# Radio_Controller.net
KiCad netlist of a schematic drawn in Altium Designer
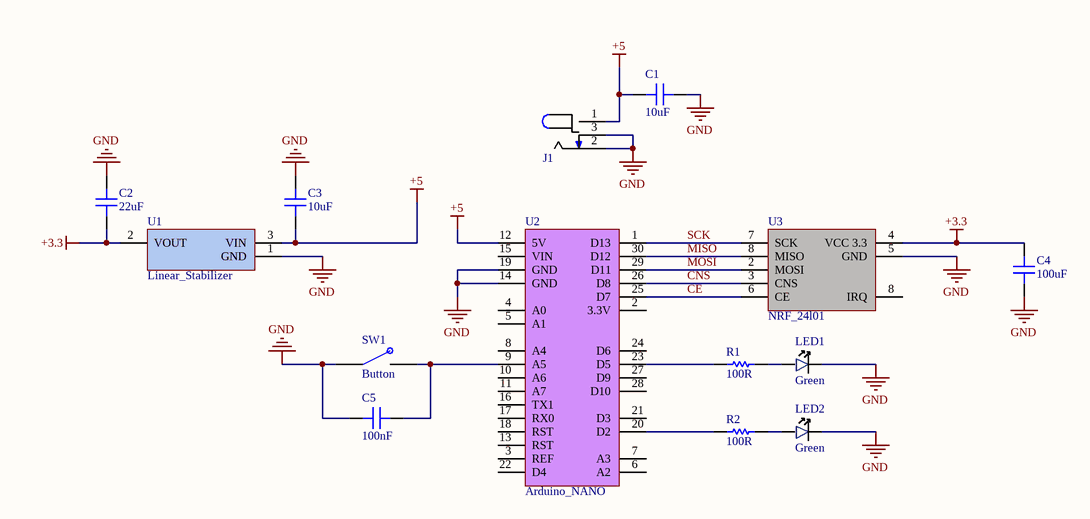
[diagram p0: Radio_Controller.SchDoc]

(export (version "E")
  (design (tool "Eeschema 10.0.6"))
  (components
    (comp (ref "C1")
      (value "10uF")
      (footprint "CAP 1206")
      (description "SMT Capacitor")
      (libsource (lib "Schlib1") (part "Capacitor"))
    )
    (comp (ref "C2")
      (value "22uF")
      (footprint "CAP 1206")
      (description "SMT Capacitor")
      (libsource (lib "Schlib1") (part "Capacitor"))
    )
    (comp (ref "C3")
      (value "10uF")
      (footprint "CAP 1206")
      (description "SMT Capacitor")
      (libsource (lib "Schlib1") (part "Capacitor"))
    )
    (comp (ref "C4")
      (value "100uF")
      (footprint "CAP 1206")
      (description "SMT Capacitor")
      (libsource (lib "Schlib1") (part "Capacitor"))
    )
    (comp (ref "C5")
      (value "100nF")
      (footprint "CAP 0603")
      (description "SMT Capacitor")
      (libsource (lib "Schlib1") (part "Capacitor"))
    )
    (comp (ref "J1")
      (value "Power Jack")
      (footprint "Power_Jack")
      (description "Power Barrel Connector Jack 2.10mm ID (0.083\"), 5.50mm OD (0.217\") Through Hole, Right Angle")
      (fields (field (name "MFR PART #") "PJ-102A") (field (name "LCSC PART#") "C136744"))
      (libsource (lib "Radio_Controller") (part "P_Power Jack"))
    )
    (comp (ref "LED1")
      (value "Green")
      (footprint "LED_0603")
      (description "LIGHT EMITTING DIODES (LED) GREEN 520~535NM 112~258MCD@20MA TOP VIEW 0603 ROHS")
      (fields (field (name "MFR PART #") "19-217/GHC-YR1S2/3T") (field (name "LCSC PART#") "C72043"))
      (libsource (lib "Radio_Controller") (part "LED_GREEN_0603"))
    )
    (comp (ref "LED2")
      (value "Green")
      (footprint "LED_0603")
      (description "LIGHT EMITTING DIODES (LED) GREEN 520~535NM 112~258MCD@20MA TOP VIEW 0603 ROHS")
      (fields (field (name "MFR PART #") "19-217/GHC-YR1S2/3T") (field (name "LCSC PART#") "C72043"))
      (libsource (lib "Radio_Controller") (part "LED_GREEN_0603"))
    )
    (comp (ref "R1")
      (value "100R")
      (footprint "RES 0603")
      (description "Resistor")
      (fields (field (name "PUBLISHER") "Altium Limited"))
      (libsource (lib "Radio_Controller") (part "Res"))
    )
    (comp (ref "R2")
      (value "100R")
      (footprint "RES 0603")
      (description "Resistor")
      (fields (field (name "PUBLISHER") "Altium Limited"))
      (libsource (lib "Radio_Controller") (part "Res"))
    )
    (comp (ref "SW1")
      (value "Button")
      (footprint "Button")
      (libsource (lib "Radio_Controller") (part "Button"))
    )
    (comp (ref "U1")
      (value "Linear_Stabilizer")
      (footprint "TO-220")
      (libsource (lib "Schlib1") (part "Linear_Stabilizer"))
    )
    (comp (ref "U2")
      (value "Arduino_NANO")
      (footprint "MODULE_ABX00028")
      (libsource (lib "Radio_Controller") (part "Arduino_NANO"))
    )
    (comp (ref "U3")
      (value "NRF_24l01")
      (footprint "NRF24L01")
      (libsource (lib "Schlib1") (part "NRF_24l01"))
    )
  )
  (nets
    (net (code "1") (name "+3.3") (class "Default")
      (node (ref "C2") (pin "2") (pinfunction "2_2") (pintype "passive"))
      (node (ref "C4") (pin "1") (pinfunction "1_1") (pintype "passive"))
      (node (ref "U1") (pin "2") (pinfunction "VOUT_2") (pintype "passive"))
      (node (ref "U3") (pin "4") (pinfunction "VCC_3.3_4") (pintype "passive"))
    )
    (net (code "2") (name "+5") (class "Default")
      (node (ref "C1") (pin "2") (pinfunction "2_2") (pintype "passive"))
      (node (ref "C3") (pin "2") (pinfunction "2_2") (pintype "passive"))
      (node (ref "J1") (pin "1") (pinfunction "1_1") (pintype "power_in"))
      (node (ref "U1") (pin "3") (pinfunction "VIN_3") (pintype "passive"))
      (node (ref "U2") (pin "12") (pinfunction "5V_12") (pintype "passive"))
    )
    (net (code "3") (name "/CE") (class "Default")
      (node (ref "U2") (pin "25") (pinfunction "D7_25") (pintype "passive"))
      (node (ref "U3") (pin "6") (pinfunction "CE_6") (pintype "passive"))
    )
    (net (code "4") (name "/CNS") (class "Default")
      (node (ref "U2") (pin "26") (pinfunction "D8_26") (pintype "passive"))
      (node (ref "U3") (pin "3") (pinfunction "CNS_3") (pintype "passive"))
    )
    (net (code "5") (name "/MISO") (class "Default")
      (node (ref "U2") (pin "30") (pinfunction "D12_30") (pintype "passive"))
      (node (ref "U3") (pin "8") (pinfunction "MISO_8") (pintype "passive"))
    )
    (net (code "6") (name "/MOSI") (class "Default")
      (node (ref "U2") (pin "29") (pinfunction "D11_29") (pintype "passive"))
      (node (ref "U3") (pin "2") (pinfunction "MOSI_2") (pintype "passive"))
    )
    (net (code "7") (name "/SCK") (class "Default")
      (node (ref "U2") (pin "1") (pinfunction "D13_1") (pintype "passive"))
      (node (ref "U3") (pin "7") (pinfunction "SCK_7") (pintype "passive"))
    )
    (net (code "8") (name "GND") (class "Default")
      (node (ref "C1") (pin "1") (pinfunction "1_1") (pintype "passive"))
      (node (ref "C2") (pin "1") (pinfunction "1_1") (pintype "passive"))
      (node (ref "C3") (pin "1") (pinfunction "1_1") (pintype "passive"))
      (node (ref "C4") (pin "2") (pinfunction "2_2") (pintype "passive"))
      (node (ref "C5") (pin "2") (pinfunction "2_2") (pintype "passive"))
      (node (ref "J1") (pin "2") (pinfunction "2_2") (pintype "power_in"))
      (node (ref "J1") (pin "3") (pinfunction "3_3") (pintype "power_in"))
      (node (ref "LED1") (pin "2") (pinfunction "2_2") (pintype "passive"))
      (node (ref "LED2") (pin "2") (pinfunction "2_2") (pintype "passive"))
      (node (ref "SW1") (pin "1") (pinfunction "1_1") (pintype "passive"))
      (node (ref "U1") (pin "1") (pinfunction "GND_1") (pintype "passive"))
      (node (ref "U2") (pin "14") (pinfunction "GND_14") (pintype "passive"))
      (node (ref "U2") (pin "19") (pinfunction "GND_19") (pintype "passive"))
      (node (ref "U3") (pin "5") (pinfunction "GND_5") (pintype "passive"))
    )
    (net (code "9") (name "Net-(LED1-Pad1)") (class "Default")
      (node (ref "LED1") (pin "1") (pinfunction "1_1") (pintype "passive"))
      (node (ref "R1") (pin "2") (pinfunction "2_2") (pintype "passive"))
    )
    (net (code "10") (name "Net-(LED2-Pad1)") (class "Default")
      (node (ref "LED2") (pin "1") (pinfunction "1_1") (pintype "passive"))
      (node (ref "R2") (pin "2") (pinfunction "2_2") (pintype "passive"))
    )
    (net (code "11") (name "Net-(U2-A5)") (class "Default")
      (node (ref "C5") (pin "1") (pinfunction "1_1") (pintype "passive"))
      (node (ref "SW1") (pin "2") (pinfunction "2_2") (pintype "passive"))
      (node (ref "U2") (pin "9") (pinfunction "A5_9") (pintype "passive"))
    )
    (net (code "12") (name "Net-(U2-D2)") (class "Default")
      (node (ref "R2") (pin "1") (pinfunction "1_1") (pintype "passive"))
      (node (ref "U2") (pin "20") (pinfunction "D2_20") (pintype "passive"))
    )
    (net (code "13") (name "Net-(U2-D5)") (class "Default")
      (node (ref "R1") (pin "1") (pinfunction "1_1") (pintype "passive"))
      (node (ref "U2") (pin "23") (pinfunction "D5_23") (pintype "passive"))
    )
    (net (code "14") (name "unconnected-(U2-3.3V-Pad2)") (class "Default")
      (node (ref "U2") (pin "2") (pinfunction "3.3V_2") (pintype "passive"))
    )
    (net (code "15") (name "unconnected-(U2-A0-Pad4)") (class "Default")
      (node (ref "U2") (pin "4") (pinfunction "A0_4") (pintype "passive"))
    )
    (net (code "16") (name "unconnected-(U2-A1-Pad5)") (class "Default")
      (node (ref "U2") (pin "5") (pinfunction "A1_5") (pintype "passive"))
    )
    (net (code "17") (name "unconnected-(U2-A2-Pad6)") (class "Default")
      (node (ref "U2") (pin "6") (pinfunction "A2_6") (pintype "passive"))
    )
    (net (code "18") (name "unconnected-(U2-A3-Pad7)") (class "Default")
      (node (ref "U2") (pin "7") (pinfunction "A3_7") (pintype "passive"))
    )
    (net (code "19") (name "unconnected-(U2-A4-Pad8)") (class "Default")
      (node (ref "U2") (pin "8") (pinfunction "A4_8") (pintype "passive"))
    )
    (net (code "20") (name "unconnected-(U2-A6-Pad10)") (class "Default")
      (node (ref "U2") (pin "10") (pinfunction "A6_10") (pintype "passive"))
    )
    (net (code "21") (name "unconnected-(U2-A7-Pad11)") (class "Default")
      (node (ref "U2") (pin "11") (pinfunction "A7_11") (pintype "passive"))
    )
    (net (code "22") (name "unconnected-(U2-D3-Pad21)") (class "Default")
      (node (ref "U2") (pin "21") (pinfunction "D3_21") (pintype "passive"))
    )
    (net (code "23") (name "unconnected-(U2-D4-Pad22)") (class "Default")
      (node (ref "U2") (pin "22") (pinfunction "D4_22") (pintype "passive"))
    )
    (net (code "24") (name "unconnected-(U2-D6-Pad24)") (class "Default")
      (node (ref "U2") (pin "24") (pinfunction "D6_24") (pintype "passive"))
    )
    (net (code "25") (name "unconnected-(U2-D9-Pad27)") (class "Default")
      (node (ref "U2") (pin "27") (pinfunction "D9_27") (pintype "passive"))
    )
    (net (code "26") (name "unconnected-(U2-D10-Pad28)") (class "Default")
      (node (ref "U2") (pin "28") (pinfunction "D10_28") (pintype "passive"))
    )
    (net (code "27") (name "unconnected-(U2-REF-Pad3)") (class "Default")
      (node (ref "U2") (pin "3") (pinfunction "REF_3") (pintype "passive"))
    )
    (net (code "28") (name "unconnected-(U2-RST-Pad13)") (class "Default")
      (node (ref "U2") (pin "13") (pinfunction "RST_13") (pintype "passive"))
    )
    (net (code "29") (name "unconnected-(U2-RST-Pad18)") (class "Default")
      (node (ref "U2") (pin "18") (pinfunction "RST_18") (pintype "passive"))
    )
    (net (code "30") (name "unconnected-(U2-RX0-Pad17)") (class "Default")
      (node (ref "U2") (pin "17") (pinfunction "RX0_17") (pintype "passive"))
    )
    (net (code "31") (name "unconnected-(U2-TX1-Pad16)") (class "Default")
      (node (ref "U2") (pin "16") (pinfunction "TX1_16") (pintype "passive"))
    )
    (net (code "32") (name "unconnected-(U2-VIN-Pad15)") (class "Default")
      (node (ref "U2") (pin "15") (pinfunction "VIN_15") (pintype "passive"))
    )
    (net (code "33") (name "unconnected-(U3-IRQ-Pad8)") (class "Default")
      (node (ref "U3") (pin "8") (pinfunction "IRQ_8") (pintype "passive"))
    )
  )
)
